# DSO_RAM.net
KiCad netlist of a schematic drawn in Altium Designer
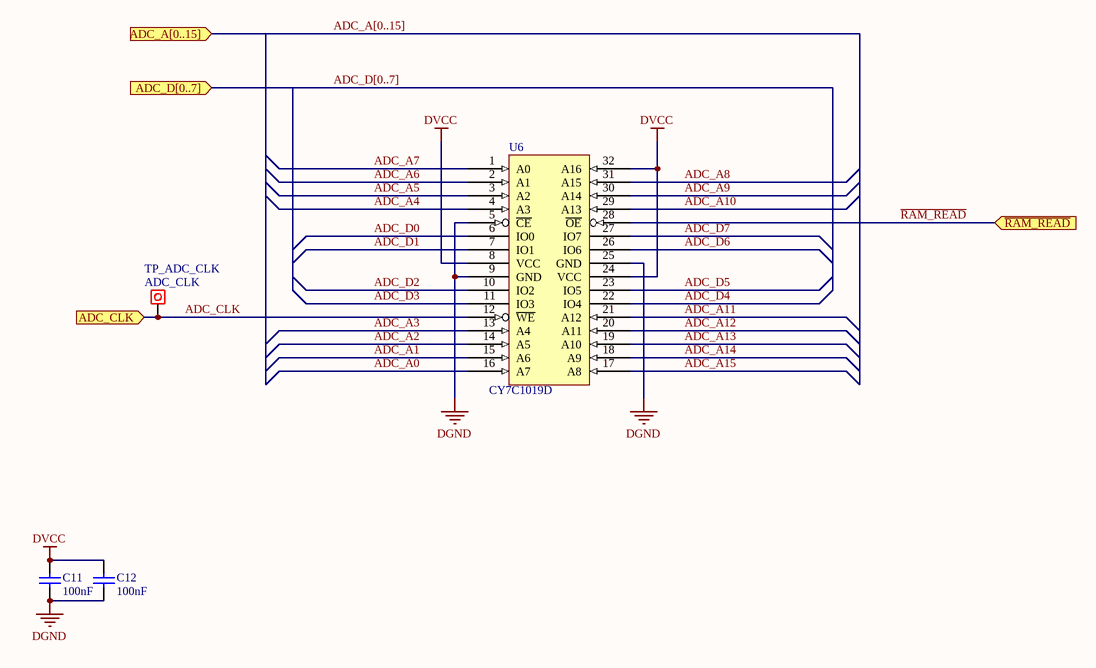
[diagram p0: DSO_RAM.SchDoc]

(export (version "E")
  (design (tool "Eeschema 10.0.6"))
  (components
    (comp (ref "C11")
      (value "100nF")
      (footprint "0805C")
      (description "Capacitor")
      (fields (field (name "REVIEWED BY") "RM - 2018/08/05"))
      (libsource (lib "DSO") (part "C"))
    )
    (comp (ref "C12")
      (value "100nF")
      (footprint "0805C")
      (description "Capacitor")
      (fields (field (name "REVIEWED BY") "RM - 2018/08/05"))
      (libsource (lib "DSO") (part "C"))
    )
    (comp (ref "TP_ADC_CLK")
      (value "ADC_CLK")
      (footprint "Testpoin")
      (description "Pad")
      (fields (field (name "Comment") "INPUT"))
      (libsource (lib "DSO") (part "Test Point"))
    )
    (comp (ref "U6")
      (value "CY7C1019D")
      (footprint "TSOP-32")
      (description "SRAM 128k x 8")
      (fields (field (name "REVIEWED BY") "RM - 2018/08/05"))
      (libsource (lib "DSO") (part "CY7C1019D"))
    )
  )
  (nets
    (net (code "1") (name "/ADC_A0") (class "Default")
      (node (ref "U6") (pin "16") (pinfunction "A7_16") (pintype "input"))
    )
    (net (code "2") (name "/ADC_A1") (class "Default")
      (node (ref "U6") (pin "15") (pinfunction "A6_15") (pintype "input"))
    )
    (net (code "3") (name "/ADC_A2") (class "Default")
      (node (ref "U6") (pin "14") (pinfunction "A5_14") (pintype "input"))
    )
    (net (code "4") (name "/ADC_A3") (class "Default")
      (node (ref "U6") (pin "13") (pinfunction "A4_13") (pintype "input"))
    )
    (net (code "5") (name "/ADC_A4") (class "Default")
      (node (ref "U6") (pin "4") (pinfunction "A3_4") (pintype "input"))
    )
    (net (code "6") (name "/ADC_A5") (class "Default")
      (node (ref "U6") (pin "3") (pinfunction "A2_3") (pintype "input"))
    )
    (net (code "7") (name "/ADC_A6") (class "Default")
      (node (ref "U6") (pin "2") (pinfunction "A1_2") (pintype "input"))
    )
    (net (code "8") (name "/ADC_A7") (class "Default")
      (node (ref "U6") (pin "1") (pinfunction "A0_1") (pintype "input"))
    )
    (net (code "9") (name "/ADC_A8") (class "Default")
      (node (ref "U6") (pin "31") (pinfunction "A15_31") (pintype "input"))
    )
    (net (code "10") (name "/ADC_A9") (class "Default")
      (node (ref "U6") (pin "30") (pinfunction "A14_30") (pintype "input"))
    )
    (net (code "11") (name "/ADC_A10") (class "Default")
      (node (ref "U6") (pin "29") (pinfunction "A13_29") (pintype "input"))
    )
    (net (code "12") (name "/ADC_A11") (class "Default")
      (node (ref "U6") (pin "21") (pinfunction "A12_21") (pintype "input"))
    )
    (net (code "13") (name "/ADC_A12") (class "Default")
      (node (ref "U6") (pin "20") (pinfunction "A11_20") (pintype "input"))
    )
    (net (code "14") (name "/ADC_A13") (class "Default")
      (node (ref "U6") (pin "19") (pinfunction "A10_19") (pintype "input"))
    )
    (net (code "15") (name "/ADC_A14") (class "Default")
      (node (ref "U6") (pin "18") (pinfunction "A9_18") (pintype "input"))
    )
    (net (code "16") (name "/ADC_A15") (class "Default")
      (node (ref "U6") (pin "17") (pinfunction "A8_17") (pintype "input"))
    )
    (net (code "18") (name "/ADC_CLK") (class "Default")
      (node (ref "TP_ADC_CLK") (pin "1") (pintype "passive"))
      (node (ref "U6") (pin "12") (pinfunction "~{WE}_12") (pintype "input"))
    )
    (net (code "19") (name "/ADC_D0") (class "Default")
      (node (ref "U6") (pin "6") (pinfunction "IO0_6") (pintype "tri_state"))
    )
    (net (code "20") (name "/ADC_D1") (class "Default")
      (node (ref "U6") (pin "7") (pinfunction "IO1_7") (pintype "tri_state"))
    )
    (net (code "21") (name "/ADC_D2") (class "Default")
      (node (ref "U6") (pin "10") (pinfunction "IO2_10") (pintype "tri_state"))
    )
    (net (code "22") (name "/ADC_D3") (class "Default")
      (node (ref "U6") (pin "11") (pinfunction "IO3_11") (pintype "tri_state"))
    )
    (net (code "23") (name "/ADC_D4") (class "Default")
      (node (ref "U6") (pin "22") (pinfunction "IO4_22") (pintype "tri_state"))
    )
    (net (code "24") (name "/ADC_D5") (class "Default")
      (node (ref "U6") (pin "23") (pinfunction "IO5_23") (pintype "tri_state"))
    )
    (net (code "25") (name "/ADC_D6") (class "Default")
      (node (ref "U6") (pin "26") (pinfunction "IO6_26") (pintype "tri_state"))
    )
    (net (code "26") (name "/ADC_D7") (class "Default")
      (node (ref "U6") (pin "27") (pinfunction "IO7_27") (pintype "tri_state"))
    )
    (net (code "28") (name "/~{RAM_READ}") (class "Default")
      (node (ref "U6") (pin "28") (pinfunction "~{OE}_28") (pintype "input"))
    )
    (net (code "29") (name "DGND") (class "Default")
      (node (ref "C11") (pin "2") (pinfunction "2_2") (pintype "passive"))
      (node (ref "C12") (pin "2") (pinfunction "2_2") (pintype "passive"))
      (node (ref "U6") (pin "25") (pinfunction "GND_25") (pintype "passive"))
      (node (ref "U6") (pin "5") (pinfunction "~{CE}_5") (pintype "input"))
      (node (ref "U6") (pin "9") (pinfunction "GND_9") (pintype "passive"))
    )
    (net (code "30") (name "DVCC") (class "Default")
      (node (ref "C11") (pin "1") (pinfunction "1_1") (pintype "passive"))
      (node (ref "C12") (pin "1") (pinfunction "1_1") (pintype "passive"))
      (node (ref "U6") (pin "24") (pinfunction "VCC_24") (pintype "passive"))
      (node (ref "U6") (pin "32") (pinfunction "A16_32") (pintype "input"))
      (node (ref "U6") (pin "8") (pinfunction "VCC_8") (pintype "passive"))
    )
  )
)
